# MCU.net
KiCad netlist of a schematic drawn in Altium Designer
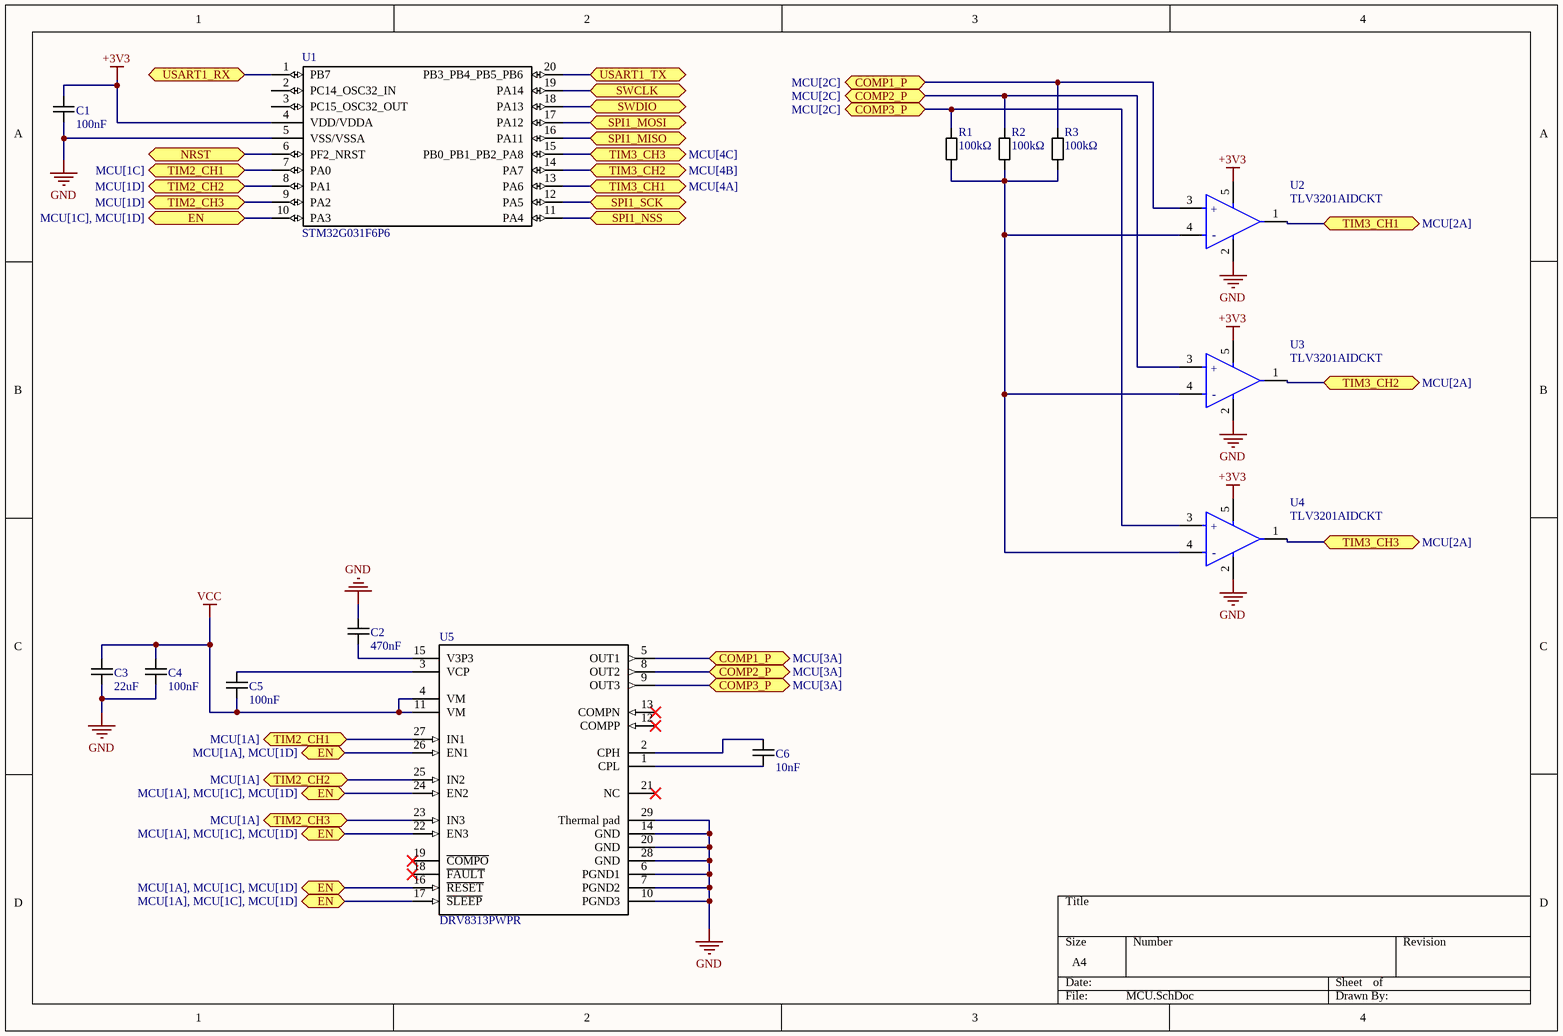
[diagram p0: MCU.SchDoc]

(export (version "E")
  (design (tool "Eeschema 10.0.6"))
  (components
    (comp (ref "C1")
      (value "100nF")
      (footprint "Capacitor 0603")
      (description "Generic 0603 Capacitor")
      (libsource (lib "Generic") (part "Capacitor 0603"))
    )
    (comp (ref "C2")
      (value "470nF")
      (footprint "Capacitor 0603")
      (description "Generic 0603 Capacitor")
      (libsource (lib "Generic") (part "Capacitor 0603"))
    )
    (comp (ref "C3")
      (value "22uF")
      (footprint "Capacitor 0603")
      (description "Generic 0603 Capacitor")
      (libsource (lib "Generic") (part "Capacitor 0603"))
    )
    (comp (ref "C4")
      (value "100nF")
      (footprint "Capacitor 0603")
      (description "Generic 0603 Capacitor")
      (libsource (lib "Generic") (part "Capacitor 0603"))
    )
    (comp (ref "C5")
      (value "100nF")
      (footprint "Capacitor 0603")
      (description "Generic 0603 Capacitor")
      (libsource (lib "Generic") (part "Capacitor 0603"))
    )
    (comp (ref "C6")
      (value "10nF")
      (footprint "Capacitor 0603")
      (description "Generic 0603 Capacitor")
      (libsource (lib "Generic") (part "Capacitor 0603"))
    )
    (comp (ref "R1")
      (value "100kΩ")
      (footprint "Resistor 0603")
      (description "Generic 0603 Resistor")
      (libsource (lib "Generic") (part "Resistor 0603"))
    )
    (comp (ref "R2")
      (value "100kΩ")
      (footprint "Resistor 0603")
      (description "Generic 0603 Resistor")
      (libsource (lib "Generic") (part "Resistor 0603"))
    )
    (comp (ref "R3")
      (value "100kΩ")
      (footprint "Resistor 0603")
      (description "Generic 0603 Resistor")
      (libsource (lib "Generic") (part "Resistor 0603"))
    )
    (comp (ref "U1")
      (value "STM32G031F6P6")
      (footprint "TSSOP20")
      (libsource (lib "Generic") (part "STM32G031F6P6"))
    )
    (comp (ref "U2")
      (value "TLV3201AIDCKT")
      (footprint "SC70")
      (description "IC COMPARATOR RRI SGL SC70-5")
      (libsource (lib "Generic") (part "TLV3201AIDCKT"))
    )
    (comp (ref "U3")
      (value "TLV3201AIDCKT")
      (footprint "SC70")
      (description "IC COMPARATOR RRI SGL SC70-5")
      (libsource (lib "Generic") (part "TLV3201AIDCKT"))
    )
    (comp (ref "U4")
      (value "TLV3201AIDCKT")
      (footprint "SC70")
      (description "IC COMPARATOR RRI SGL SC70-5")
      (libsource (lib "Generic") (part "TLV3201AIDCKT"))
    )
    (comp (ref "U5")
      (value "DRV8313PWPR")
      (footprint "FP-PWP0028C-IPC_A")
      (description "IC MOTOR DRIVER 8V-60V 28HTSSOP")
      (libsource (lib "Generic") (part "CMP-04915-000025-1"))
    )
  )
  (nets
    (net (code "1") (name "+3V3") (class "Default")
      (node (ref "C1") (pin "2") (pinfunction "2_2") (pintype "passive"))
      (node (ref "U1") (pin "4") (pinfunction "VDD/VDDA_4") (pintype "power_in"))
      (node (ref "U2") (pin "5") (pinfunction "VCC_5") (pintype "power_in"))
      (node (ref "U3") (pin "5") (pinfunction "VCC_5") (pintype "power_in"))
      (node (ref "U4") (pin "5") (pinfunction "VCC_5") (pintype "power_in"))
    )
    (net (code "2") (name "/COMP1_P") (class "Default")
      (node (ref "R3") (pin "2") (pintype "passive"))
      (node (ref "U2") (pin "3") (pinfunction "IN+_3") (pintype "tri_state"))
      (node (ref "U5") (pin "5") (pinfunction "OUT1_5") (pintype "output"))
    )
    (net (code "3") (name "/COMP2_P") (class "Default")
      (node (ref "R2") (pin "2") (pintype "passive"))
      (node (ref "U3") (pin "3") (pinfunction "IN+_3") (pintype "tri_state"))
      (node (ref "U5") (pin "8") (pinfunction "OUT2_8") (pintype "output"))
    )
    (net (code "4") (name "/COMP3_P") (class "Default")
      (node (ref "R1") (pin "2") (pintype "passive"))
      (node (ref "U4") (pin "3") (pinfunction "IN+_3") (pintype "tri_state"))
      (node (ref "U5") (pin "9") (pinfunction "OUT3_9") (pintype "output"))
    )
    (net (code "5") (name "/EN") (class "Default")
      (node (ref "U1") (pin "10") (pinfunction "PA3_10") (pintype "bidirectional"))
      (node (ref "U5") (pin "16") (pinfunction "~{RESET}_16") (pintype "input"))
      (node (ref "U5") (pin "17") (pinfunction "~{SLEEP}_17") (pintype "input"))
      (node (ref "U5") (pin "22") (pinfunction "EN3_22") (pintype "input"))
      (node (ref "U5") (pin "24") (pinfunction "EN2_24") (pintype "input"))
      (node (ref "U5") (pin "26") (pinfunction "EN1_26") (pintype "input"))
    )
    (net (code "6") (name "/NRST") (class "Default")
      (node (ref "U1") (pin "6") (pinfunction "PF2_NRST_6") (pintype "bidirectional"))
    )
    (net (code "7") (name "/SPI1_MISO") (class "Default")
      (node (ref "U1") (pin "16") (pinfunction "PA11_16") (pintype "bidirectional"))
    )
    (net (code "8") (name "/SPI1_MOSI") (class "Default")
      (node (ref "U1") (pin "17") (pinfunction "PA12_17") (pintype "bidirectional"))
    )
    (net (code "9") (name "/SPI1_NSS") (class "Default")
      (node (ref "U1") (pin "11") (pinfunction "PA4_11") (pintype "bidirectional"))
    )
    (net (code "10") (name "/SPI1_SCK") (class "Default")
      (node (ref "U1") (pin "12") (pinfunction "PA5_12") (pintype "bidirectional"))
    )
    (net (code "11") (name "/SWCLK") (class "Default")
      (node (ref "U1") (pin "19") (pinfunction "PA14_19") (pintype "bidirectional"))
    )
    (net (code "12") (name "/SWDIO") (class "Default")
      (node (ref "U1") (pin "18") (pinfunction "PA13_18") (pintype "bidirectional"))
    )
    (net (code "13") (name "/TIM2_CH1") (class "Default")
      (node (ref "U1") (pin "7") (pinfunction "PA0_7") (pintype "bidirectional"))
      (node (ref "U5") (pin "27") (pinfunction "IN1_27") (pintype "input"))
    )
    (net (code "14") (name "/TIM2_CH2") (class "Default")
      (node (ref "U1") (pin "8") (pinfunction "PA1_8") (pintype "bidirectional"))
      (node (ref "U5") (pin "25") (pinfunction "IN2_25") (pintype "input"))
    )
    (net (code "15") (name "/TIM2_CH3") (class "Default")
      (node (ref "U1") (pin "9") (pinfunction "PA2_9") (pintype "bidirectional"))
      (node (ref "U5") (pin "23") (pinfunction "IN3_23") (pintype "input"))
    )
    (net (code "16") (name "/TIM3_CH1") (class "Default")
      (node (ref "U1") (pin "13") (pinfunction "PA6_13") (pintype "bidirectional"))
      (node (ref "U2") (pin "1") (pinfunction "OUT_1") (pintype "passive"))
    )
    (net (code "17") (name "/TIM3_CH2") (class "Default")
      (node (ref "U1") (pin "14") (pinfunction "PA7_14") (pintype "bidirectional"))
      (node (ref "U3") (pin "1") (pinfunction "OUT_1") (pintype "passive"))
    )
    (net (code "18") (name "/TIM3_CH3") (class "Default")
      (node (ref "U1") (pin "15") (pinfunction "PB0_PB1_PB2_PA8_15") (pintype "bidirectional"))
      (node (ref "U4") (pin "1") (pinfunction "OUT_1") (pintype "passive"))
    )
    (net (code "19") (name "/USART1_RX") (class "Default")
      (node (ref "U1") (pin "1") (pinfunction "PB7_1") (pintype "bidirectional"))
    )
    (net (code "20") (name "/USART1_TX") (class "Default")
      (node (ref "U1") (pin "20") (pinfunction "PB3_PB4_PB5_PB6_20") (pintype "bidirectional"))
    )
    (net (code "21") (name "GND") (class "Default")
      (node (ref "C1") (pin "1") (pinfunction "1_1") (pintype "passive"))
      (node (ref "C2") (pin "2") (pinfunction "2_2") (pintype "passive"))
      (node (ref "C3") (pin "1") (pinfunction "1_1") (pintype "passive"))
      (node (ref "C4") (pin "1") (pinfunction "1_1") (pintype "passive"))
      (node (ref "U1") (pin "5") (pinfunction "VSS/VSSA_5") (pintype "power_in"))
      (node (ref "U2") (pin "2") (pinfunction "GND_2") (pintype "power_in"))
      (node (ref "U3") (pin "2") (pinfunction "GND_2") (pintype "power_in"))
      (node (ref "U4") (pin "2") (pinfunction "GND_2") (pintype "power_in"))
      (node (ref "U5") (pin "10") (pinfunction "PGND3_10") (pintype "power_in"))
      (node (ref "U5") (pin "14") (pinfunction "GND_14") (pintype "power_in"))
      (node (ref "U5") (pin "20") (pinfunction "GND_20") (pintype "power_in"))
      (node (ref "U5") (pin "28") (pinfunction "GND_28") (pintype "power_in"))
      (node (ref "U5") (pin "29") (pinfunction "Thermal_pad_29") (pintype "power_in"))
      (node (ref "U5") (pin "6") (pinfunction "PGND1_6") (pintype "power_in"))
      (node (ref "U5") (pin "7") (pinfunction "PGND2_7") (pintype "power_in"))
    )
    (net (code "22") (name "Net-(U2-IN-)") (class "Default")
      (node (ref "R1") (pin "1") (pintype "passive"))
      (node (ref "R2") (pin "1") (pintype "passive"))
      (node (ref "R3") (pin "1") (pintype "passive"))
      (node (ref "U2") (pin "4") (pinfunction "IN-_4") (pintype "tri_state"))
      (node (ref "U3") (pin "4") (pinfunction "IN-_4") (pintype "tri_state"))
      (node (ref "U4") (pin "4") (pinfunction "IN-_4") (pintype "tri_state"))
    )
    (net (code "23") (name "Net-(U5-CPH)") (class "Default")
      (node (ref "C6") (pin "2") (pinfunction "2_2") (pintype "passive"))
      (node (ref "U5") (pin "2") (pinfunction "CPH_2") (pintype "power_in"))
    )
    (net (code "24") (name "Net-(U5-CPL)") (class "Default")
      (node (ref "C6") (pin "1") (pinfunction "1_1") (pintype "passive"))
      (node (ref "U5") (pin "1") (pinfunction "CPL_1") (pintype "power_in"))
    )
    (net (code "25") (name "Net-(U5-V3P3)") (class "Default")
      (node (ref "C2") (pin "1") (pinfunction "1_1") (pintype "passive"))
      (node (ref "U5") (pin "15") (pinfunction "V3P3_15") (pintype "power_in"))
    )
    (net (code "26") (name "Net-(U5-VCP)") (class "Default")
      (node (ref "C5") (pin "2") (pinfunction "2_2") (pintype "passive"))
      (node (ref "U5") (pin "3") (pinfunction "VCP_3") (pintype "power_in"))
    )
    (net (code "27") (name "VCC") (class "Default")
      (node (ref "C3") (pin "2") (pinfunction "2_2") (pintype "passive"))
      (node (ref "C4") (pin "2") (pinfunction "2_2") (pintype "passive"))
      (node (ref "C5") (pin "1") (pinfunction "1_1") (pintype "passive"))
      (node (ref "U5") (pin "11") (pinfunction "VM_11") (pintype "power_in"))
      (node (ref "U5") (pin "4") (pinfunction "VM_4") (pintype "power_in"))
    )
    (net (code "28") (name "unconnected-(U1-PC14_OSC32_IN-Pad2)") (class "Default")
      (node (ref "U1") (pin "2") (pinfunction "PC14_OSC32_IN_2") (pintype "bidirectional"))
    )
    (net (code "29") (name "unconnected-(U1-PC15_OSC32_OUT-Pad3)") (class "Default")
      (node (ref "U1") (pin "3") (pinfunction "PC15_OSC32_OUT_3") (pintype "bidirectional"))
    )
    (net (code "30") (name "unconnected-(U5-COMPN-Pad13)") (class "Default")
      (node (ref "U5") (pin "13") (pinfunction "COMPN_13") (pintype "input+no_connect"))
    )
    (net (code "31") (name "unconnected-(U5-COMPP-Pad12)") (class "Default")
      (node (ref "U5") (pin "12") (pinfunction "COMPP_12") (pintype "input+no_connect"))
    )
    (net (code "32") (name "unconnected-(U5-NC-Pad21)") (class "Default")
      (node (ref "U5") (pin "21") (pinfunction "NC_21") (pintype "passive+no_connect"))
    )
    (net (code "33") (name "unconnected-(U5-~{COMPO}-Pad19)") (class "Default")
      (node (ref "U5") (pin "19") (pinfunction "~{COMPO}_19") (pintype "open_collector+no_connect"))
    )
    (net (code "34") (name "unconnected-(U5-~{FAULT}-Pad18)") (class "Default")
      (node (ref "U5") (pin "18") (pinfunction "~{FAULT}_18") (pintype "open_collector+no_connect"))
    )
  )
)
